# ETH_PART.net
KiCad netlist of a schematic drawn in Altium Designer
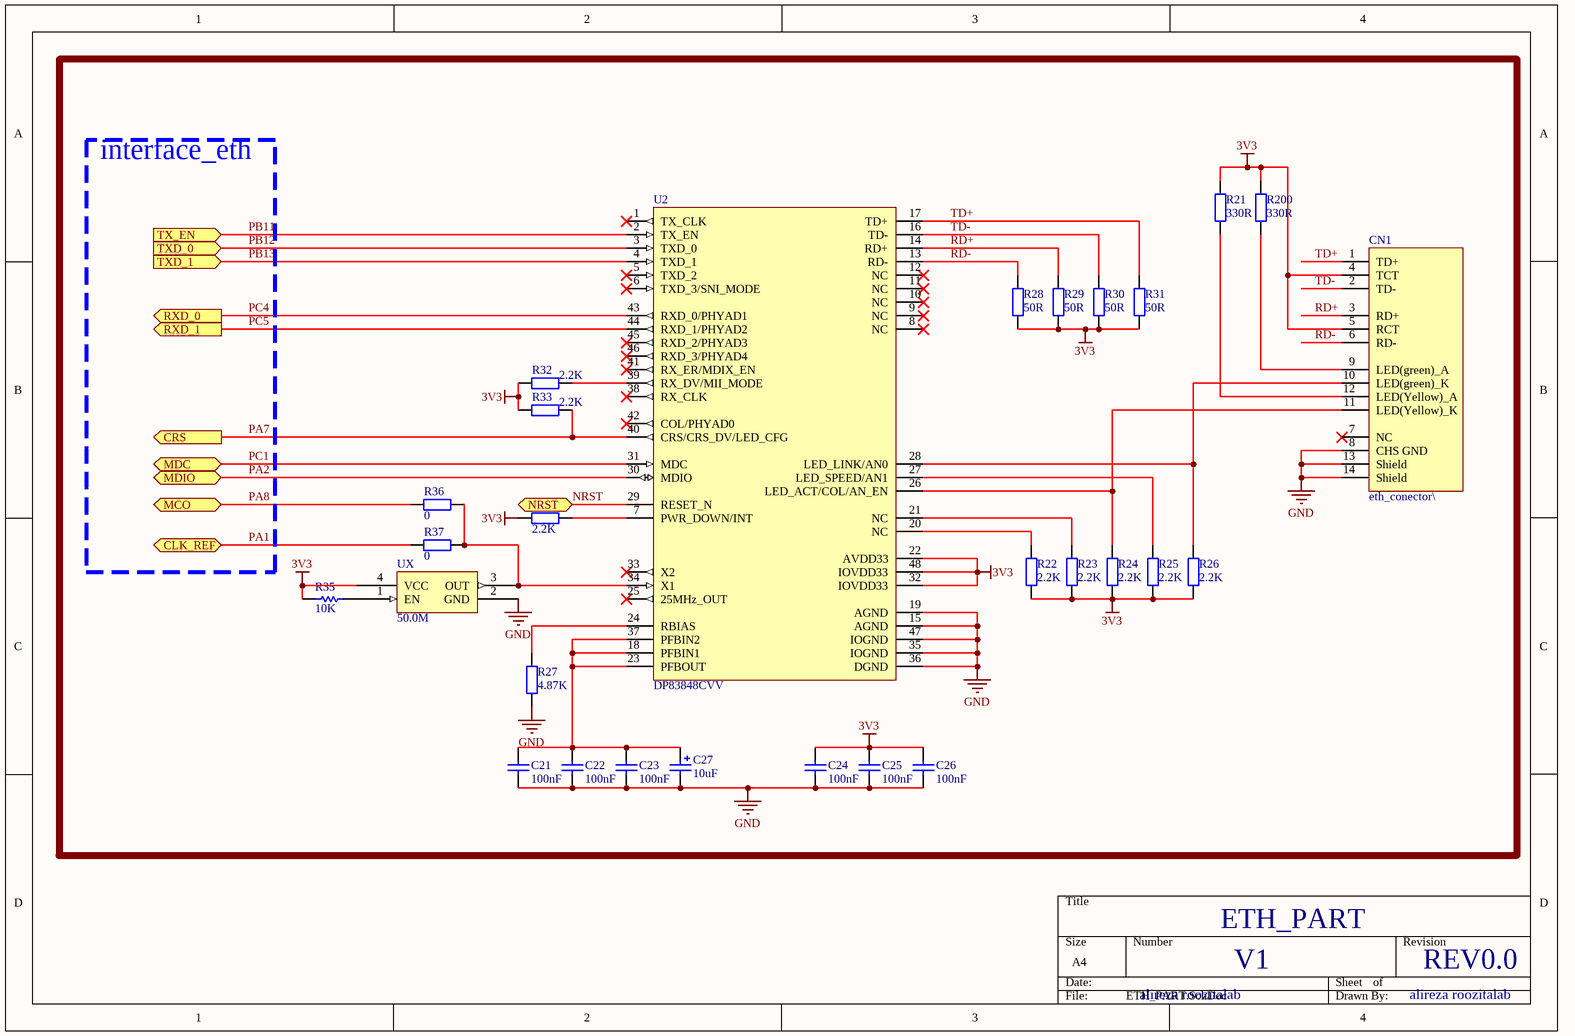
[diagram p0: ETH_PART.SchDoc]

(export (version "E")
  (design (tool "Eeschema 10.0.6"))
  (components
    (comp (ref "C21")
      (value "100nF")
      (footprint "0805.")
      (description "Capacitor")
      (fields (field (name "PUBLISHER") "Altium Limited"))
      (libsource (lib "STM32F407_144") (part "Cap"))
    )
    (comp (ref "C22")
      (value "100nF")
      (footprint "0805.")
      (description "Capacitor")
      (fields (field (name "PUBLISHER") "Altium Limited"))
      (libsource (lib "STM32F407_144") (part "Cap"))
    )
    (comp (ref "C23")
      (value "100nF")
      (footprint "0805.")
      (description "Capacitor")
      (fields (field (name "PUBLISHER") "Altium Limited"))
      (libsource (lib "STM32F407_144") (part "Cap"))
    )
    (comp (ref "C24")
      (value "100nF")
      (footprint "0805.")
      (description "Capacitor")
      (fields (field (name "PUBLISHER") "Altium Limited"))
      (libsource (lib "STM32F407_144") (part "Cap"))
    )
    (comp (ref "C25")
      (value "100nF")
      (footprint "0805.")
      (description "Capacitor")
      (fields (field (name "PUBLISHER") "Altium Limited"))
      (libsource (lib "STM32F407_144") (part "Cap"))
    )
    (comp (ref "C26")
      (value "100nF")
      (footprint "0805.")
      (description "Capacitor")
      (fields (field (name "PUBLISHER") "Altium Limited"))
      (libsource (lib "STM32F407_144") (part "Cap"))
    )
    (comp (ref "C27")
      (value "10uF")
      (footprint "C1206.")
      (description "Polarized Capacitor (Radial)")
      (fields (field (name "PUBLISHER") "Altium Limited"))
      (libsource (lib "STM32F407_144") (part "Cap Pol1"))
    )
    (comp (ref "CN1")
      (value "eth_conecto~{r}")
      (footprint "eth_conector")
      (libsource (lib "my dxp lib") (part "eth_conector{backslash}"))
    )
    (comp (ref "R21")
      (value "330R")
      (footprint "0805.")
      (description "Resistor")
      (fields (field (name "Comment") "Res2") (field (name "PUBLISHER") "Altium Limited"))
      (libsource (lib "STM32F407_144") (part "Res2"))
    )
    (comp (ref "R22")
      (value "2.2K")
      (footprint "0805.")
      (description "Resistor")
      (fields (field (name "Comment") "Res2") (field (name "PUBLISHER") "Altium Limited"))
      (libsource (lib "STM32F407_144") (part "Res2"))
    )
    (comp (ref "R23")
      (value "2.2K")
      (footprint "0805.")
      (description "Resistor")
      (fields (field (name "Comment") "Res2") (field (name "PUBLISHER") "Altium Limited"))
      (libsource (lib "STM32F407_144") (part "Res2"))
    )
    (comp (ref "R24")
      (value "2.2K")
      (footprint "0805.")
      (description "Resistor")
      (fields (field (name "Comment") "Res2") (field (name "PUBLISHER") "Altium Limited"))
      (libsource (lib "STM32F407_144") (part "Res2"))
    )
    (comp (ref "R25")
      (value "2.2K")
      (footprint "0805.")
      (description "Resistor")
      (fields (field (name "Comment") "Res2") (field (name "PUBLISHER") "Altium Limited"))
      (libsource (lib "STM32F407_144") (part "Res2"))
    )
    (comp (ref "R26")
      (value "2.2K")
      (footprint "0805.")
      (description "Resistor")
      (fields (field (name "Comment") "Res2") (field (name "PUBLISHER") "Altium Limited"))
      (libsource (lib "STM32F407_144") (part "Res2"))
    )
    (comp (ref "R27")
      (value "4.87K")
      (footprint "0805.")
      (description "Resistor")
      (fields (field (name "Comment") "Res2") (field (name "PUBLISHER") "Altium Limited"))
      (libsource (lib "STM32F407_144") (part "Res2"))
    )
    (comp (ref "R28")
      (value "50R")
      (footprint "0805.")
      (description "Resistor")
      (fields (field (name "Comment") "Res2") (field (name "PUBLISHER") "Altium Limited"))
      (libsource (lib "STM32F407_144") (part "Res2"))
    )
    (comp (ref "R29")
      (value "50R")
      (footprint "0805.")
      (description "Resistor")
      (fields (field (name "Comment") "Res2") (field (name "PUBLISHER") "Altium Limited"))
      (libsource (lib "STM32F407_144") (part "Res2"))
    )
    (comp (ref "R30")
      (value "50R")
      (footprint "0805.")
      (description "Resistor")
      (fields (field (name "Comment") "Res2") (field (name "PUBLISHER") "Altium Limited"))
      (libsource (lib "STM32F407_144") (part "Res2"))
    )
    (comp (ref "R31")
      (value "50R")
      (footprint "0805.")
      (description "Resistor")
      (fields (field (name "Comment") "Res2") (field (name "PUBLISHER") "Altium Limited"))
      (libsource (lib "STM32F407_144") (part "Res2"))
    )
    (comp (ref "R32")
      (value "2.2K")
      (footprint "0805.")
      (description "Resistor")
      (fields (field (name "Comment") "Res2") (field (name "PUBLISHER") "Altium Limited"))
      (libsource (lib "") (part "Res2_1"))
    )
    (comp (ref "R33")
      (value "2.2K")
      (footprint "0805.")
      (description "Resistor")
      (fields (field (name "Comment") "Res2") (field (name "PUBLISHER") "Altium Limited"))
      (libsource (lib "") (part "Res2_1"))
    )
    (comp (ref "R34")
      (value "2.2K")
      (footprint "0805.")
      (description "Resistor")
      (fields (field (name "Comment") "Res2") (field (name "PUBLISHER") "Altium Limited"))
      (libsource (lib "") (part "Res2_1"))
    )
    (comp (ref "R35")
      (value "10K")
      (footprint "0805.")
      (description "Resistor")
      (fields (field (name "PUBLISHER") "Altium Limited"))
      (libsource (lib "STM32F407_144") (part "Res1"))
    )
    (comp (ref "R36")
      (value "0")
      (footprint "0805.")
      (description "Resistor")
      (fields (field (name "Comment") "Res2") (field (name "PUBLISHER") "Altium Limited"))
      (libsource (lib "") (part "Res2_1"))
    )
    (comp (ref "R37")
      (value "0")
      (footprint "0805.")
      (description "Resistor")
      (fields (field (name "Comment") "Res2") (field (name "PUBLISHER") "Altium Limited"))
      (libsource (lib "") (part "Res2_1"))
    )
    (comp (ref "R200")
      (value "330R")
      (footprint "0805.")
      (description "Resistor")
      (fields (field (name "Comment") "Res2") (field (name "PUBLISHER") "Altium Limited"))
      (libsource (lib "STM32F407_144") (part "Res2"))
    )
    (comp (ref "U2")
      (value "DP83848CVV")
      (footprint "LQFP48")
      (libsource (lib "STM32F407_144") (part "DP83848CVV"))
    )
    (comp (ref "UX")
      (value "50.0M")
      (footprint "oscillator_50MHZ")
      (libsource (lib "STM32F407_144") (part "SM7745HEV-50.0M"))
    )
  )
  (nets
    (net (code "1") (name "/NRST") (class "Default")
      (node (ref "U2") (pin "29") (pinfunction "RESET_N_29") (pintype "passive"))
    )
    (net (code "2") (name "/PA1") (class "Default")
      (node (ref "R37") (pin "1") (pinfunction "1_1") (pintype "passive"))
    )
    (net (code "3") (name "/PA2") (class "Default")
      (node (ref "U2") (pin "30") (pinfunction "MDIO_30") (pintype "bidirectional"))
    )
    (net (code "4") (name "/PA7") (class "Default")
      (node (ref "R33") (pin "2") (pinfunction "2_2") (pintype "passive"))
      (node (ref "U2") (pin "40") (pinfunction "CRS/CRS_DV/LED_CFG_40") (pintype "output"))
    )
    (net (code "5") (name "/PA8") (class "Default")
      (node (ref "R36") (pin "1") (pinfunction "1_1") (pintype "passive"))
    )
    (net (code "6") (name "/PB11") (class "Default")
      (node (ref "U2") (pin "2") (pinfunction "TX_EN_2") (pintype "input"))
    )
    (net (code "7") (name "/PB12") (class "Default")
      (node (ref "U2") (pin "3") (pinfunction "TXD_0_3") (pintype "input"))
    )
    (net (code "8") (name "/PB13") (class "Default")
      (node (ref "U2") (pin "4") (pinfunction "TXD_1_4") (pintype "input"))
    )
    (net (code "9") (name "/PC1") (class "Default")
      (node (ref "U2") (pin "31") (pinfunction "MDC_31") (pintype "input"))
    )
    (net (code "10") (name "/PC4") (class "Default")
      (node (ref "U2") (pin "43") (pinfunction "RXD_0/PHYAD1_43") (pintype "output"))
    )
    (net (code "11") (name "/PC5") (class "Default")
      (node (ref "U2") (pin "44") (pinfunction "RXD_1/PHYAD2_44") (pintype "output"))
    )
    (net (code "12") (name "/RD+") (class "Default")
      (node (ref "CN1") (pin "3") (pinfunction "RD+_3") (pintype "passive"))
      (node (ref "R29") (pin "2") (pinfunction "2_2") (pintype "passive"))
      (node (ref "U2") (pin "14") (pinfunction "RD+_14") (pintype "passive"))
    )
    (net (code "13") (name "/RD-") (class "Default")
      (node (ref "CN1") (pin "6") (pinfunction "RD-_6") (pintype "passive"))
      (node (ref "R28") (pin "2") (pinfunction "2_2") (pintype "passive"))
      (node (ref "U2") (pin "13") (pinfunction "RD-_13") (pintype "passive"))
    )
    (net (code "14") (name "/TD+") (class "Default")
      (node (ref "CN1") (pin "1") (pinfunction "TD+_1") (pintype "passive"))
      (node (ref "R31") (pin "2") (pinfunction "2_2") (pintype "passive"))
      (node (ref "U2") (pin "17") (pinfunction "TD+_17") (pintype "passive"))
    )
    (net (code "15") (name "/TD-") (class "Default")
      (node (ref "CN1") (pin "2") (pinfunction "TD-_2") (pintype "passive"))
      (node (ref "R30") (pin "2") (pinfunction "2_2") (pintype "passive"))
      (node (ref "U2") (pin "16") (pinfunction "TD-_16") (pintype "passive"))
    )
    (net (code "16") (name "3V3") (class "Default")
      (node (ref "C24") (pin "1") (pinfunction "1_1") (pintype "passive"))
      (node (ref "C25") (pin "1") (pinfunction "1_1") (pintype "passive"))
      (node (ref "C26") (pin "1") (pinfunction "1_1") (pintype "passive"))
      (node (ref "CN1") (pin "4") (pinfunction "TCT_4") (pintype "passive"))
      (node (ref "CN1") (pin "5") (pinfunction "RCT_5") (pintype "passive"))
      (node (ref "R200") (pin "2") (pinfunction "2_2") (pintype "passive"))
      (node (ref "R21") (pin "2") (pinfunction "2_2") (pintype "passive"))
      (node (ref "R22") (pin "1") (pinfunction "1_1") (pintype "passive"))
      (node (ref "R23") (pin "1") (pinfunction "1_1") (pintype "passive"))
      (node (ref "R24") (pin "1") (pinfunction "1_1") (pintype "passive"))
      (node (ref "R25") (pin "1") (pinfunction "1_1") (pintype "passive"))
      (node (ref "R26") (pin "1") (pinfunction "1_1") (pintype "passive"))
      (node (ref "R28") (pin "1") (pinfunction "1_1") (pintype "passive"))
      (node (ref "R29") (pin "1") (pinfunction "1_1") (pintype "passive"))
      (node (ref "R30") (pin "1") (pinfunction "1_1") (pintype "passive"))
      (node (ref "R31") (pin "1") (pinfunction "1_1") (pintype "passive"))
      (node (ref "R32") (pin "1") (pinfunction "1_1") (pintype "passive"))
      (node (ref "R33") (pin "1") (pinfunction "1_1") (pintype "passive"))
      (node (ref "R34") (pin "1") (pinfunction "1_1") (pintype "passive"))
      (node (ref "R35") (pin "1") (pinfunction "1_1") (pintype "passive"))
      (node (ref "U2") (pin "22") (pinfunction "AVDD33_22") (pintype "passive"))
      (node (ref "U2") (pin "32") (pinfunction "IOVDD33_32") (pintype "passive"))
      (node (ref "U2") (pin "48") (pinfunction "IOVDD33_48") (pintype "passive"))
      (node (ref "UX") (pin "4") (pinfunction "VCC_4") (pintype "passive"))
    )
    (net (code "17") (name "GND") (class "Default")
      (node (ref "C21") (pin "2") (pinfunction "2_2") (pintype "passive"))
      (node (ref "C22") (pin "2") (pinfunction "2_2") (pintype "passive"))
      (node (ref "C23") (pin "2") (pinfunction "2_2") (pintype "passive"))
      (node (ref "C24") (pin "2") (pinfunction "2_2") (pintype "passive"))
      (node (ref "C25") (pin "2") (pinfunction "2_2") (pintype "passive"))
      (node (ref "C26") (pin "2") (pinfunction "2_2") (pintype "passive"))
      (node (ref "C27") (pin "2") (pinfunction "2_2") (pintype "passive"))
      (node (ref "CN1") (pin "13") (pinfunction "Shield_13") (pintype "passive"))
      (node (ref "CN1") (pin "14") (pinfunction "Shield_14") (pintype "passive"))
      (node (ref "CN1") (pin "8") (pinfunction "CHS_GND_8") (pintype "passive"))
      (node (ref "R27") (pin "1") (pinfunction "1_1") (pintype "passive"))
      (node (ref "U2") (pin "15") (pinfunction "AGND_15") (pintype "passive"))
      (node (ref "U2") (pin "19") (pinfunction "AGND_19") (pintype "passive"))
      (node (ref "U2") (pin "35") (pinfunction "IOGND_35") (pintype "passive"))
      (node (ref "U2") (pin "36") (pinfunction "DGND_36") (pintype "passive"))
      (node (ref "U2") (pin "47") (pinfunction "IOGND_47") (pintype "passive"))
      (node (ref "UX") (pin "2") (pinfunction "GND_2") (pintype "passive"))
    )
    (net (code "18") (name "Net-(CN1-LED(Yellow)_A)") (class "Default")
      (node (ref "CN1") (pin "12") (pinfunction "LED(Yellow)_A_12") (pintype "passive"))
      (node (ref "R21") (pin "1") (pinfunction "1_1") (pintype "passive"))
    )
    (net (code "19") (name "Net-(CN1-LED(Yellow)_K)") (class "Default")
      (node (ref "CN1") (pin "11") (pinfunction "LED(Yellow)_K_11") (pintype "passive"))
      (node (ref "R24") (pin "2") (pinfunction "2_2") (pintype "passive"))
      (node (ref "U2") (pin "26") (pinfunction "LED_ACT/COL/AN_EN_26") (pintype "passive"))
    )
    (net (code "20") (name "Net-(CN1-LED(green)_A)") (class "Default")
      (node (ref "CN1") (pin "9") (pinfunction "LED(green)_A_9") (pintype "passive"))
      (node (ref "R200") (pin "1") (pinfunction "1_1") (pintype "passive"))
    )
    (net (code "21") (name "Net-(CN1-LED(green)_K)") (class "Default")
      (node (ref "CN1") (pin "10") (pinfunction "LED(green)_K_10") (pintype "passive"))
      (node (ref "R26") (pin "2") (pinfunction "2_2") (pintype "passive"))
      (node (ref "U2") (pin "28") (pinfunction "LED_LINK/AN0_28") (pintype "passive"))
    )
    (net (code "22") (name "Net-(R22-Pad2)") (class "Default")
      (node (ref "R22") (pin "2") (pinfunction "2_2") (pintype "passive"))
      (node (ref "U2") (pin "20") (pinfunction "NC_20") (pintype "passive"))
    )
    (net (code "23") (name "Net-(R23-Pad2)") (class "Default")
      (node (ref "R23") (pin "2") (pinfunction "2_2") (pintype "passive"))
      (node (ref "U2") (pin "21") (pinfunction "NC_21") (pintype "passive"))
    )
    (net (code "24") (name "Net-(U2-LED_SPEED{slash}AN1)") (class "Default")
      (node (ref "R25") (pin "2") (pinfunction "2_2") (pintype "passive"))
      (node (ref "U2") (pin "27") (pinfunction "LED_SPEED/AN1_27") (pintype "passive"))
    )
    (net (code "25") (name "Net-(U2-PFBIN1)") (class "Default")
      (node (ref "C21") (pin "1") (pinfunction "1_1") (pintype "passive"))
      (node (ref "C22") (pin "1") (pinfunction "1_1") (pintype "passive"))
      (node (ref "C23") (pin "1") (pinfunction "1_1") (pintype "passive"))
      (node (ref "C27") (pin "1") (pinfunction "1_1") (pintype "passive"))
      (node (ref "U2") (pin "18") (pinfunction "PFBIN1_18") (pintype "passive"))
      (node (ref "U2") (pin "23") (pinfunction "PFBOUT_23") (pintype "passive"))
      (node (ref "U2") (pin "37") (pinfunction "PFBIN2_37") (pintype "passive"))
    )
    (net (code "26") (name "Net-(U2-PWR_DOWN{slash}INT)") (class "Default")
      (node (ref "R34") (pin "2") (pinfunction "2_2") (pintype "passive"))
      (node (ref "U2") (pin "7") (pinfunction "PWR_DOWN/INT_7") (pintype "passive"))
    )
    (net (code "27") (name "Net-(U2-RBIAS)") (class "Default")
      (node (ref "R27") (pin "2") (pinfunction "2_2") (pintype "passive"))
      (node (ref "U2") (pin "24") (pinfunction "RBIAS_24") (pintype "passive"))
    )
    (net (code "28") (name "Net-(U2-RX_DV{slash}MII_MODE)") (class "Default")
      (node (ref "R32") (pin "2") (pinfunction "2_2") (pintype "passive"))
      (node (ref "U2") (pin "39") (pinfunction "RX_DV/MII_MODE_39") (pintype "output"))
    )
    (net (code "29") (name "Net-(U2-X1)") (class "Default")
      (node (ref "R36") (pin "2") (pinfunction "2_2") (pintype "passive"))
      (node (ref "R37") (pin "2") (pinfunction "2_2") (pintype "passive"))
      (node (ref "U2") (pin "34") (pinfunction "X1_34") (pintype "input"))
      (node (ref "UX") (pin "3") (pinfunction "OUT_3") (pintype "output"))
    )
    (net (code "30") (name "Net-(UX-EN)") (class "Default")
      (node (ref "R35") (pin "2") (pinfunction "2_2") (pintype "passive"))
      (node (ref "UX") (pin "1") (pinfunction "EN_1") (pintype "input"))
    )
    (net (code "31") (name "unconnected-(CN1-NC-Pad7)") (class "Default")
      (node (ref "CN1") (pin "7") (pinfunction "NC_7") (pintype "passive+no_connect"))
    )
    (net (code "32") (name "unconnected-(U2-25MHz_OUT-Pad25)") (class "Default")
      (node (ref "U2") (pin "25") (pinfunction "25MHz_OUT_25") (pintype "output+no_connect"))
    )
    (net (code "33") (name "unconnected-(U2-COL{slash}PHYAD0-Pad42)") (class "Default")
      (node (ref "U2") (pin "42") (pinfunction "COL/PHYAD0_42") (pintype "output+no_connect"))
    )
    (net (code "34") (name "unconnected-(U2-NC-Pad8)") (class "Default")
      (node (ref "U2") (pin "8") (pinfunction "NC_8") (pintype "passive+no_connect"))
    )
    (net (code "35") (name "unconnected-(U2-NC-Pad9)") (class "Default")
      (node (ref "U2") (pin "9") (pinfunction "NC_9") (pintype "passive+no_connect"))
    )
    (net (code "36") (name "unconnected-(U2-NC-Pad10)") (class "Default")
      (node (ref "U2") (pin "10") (pinfunction "NC_10") (pintype "passive+no_connect"))
    )
    (net (code "37") (name "unconnected-(U2-NC-Pad11)") (class "Default")
      (node (ref "U2") (pin "11") (pinfunction "NC_11") (pintype "passive+no_connect"))
    )
    (net (code "38") (name "unconnected-(U2-NC-Pad12)") (class "Default")
      (node (ref "U2") (pin "12") (pinfunction "NC_12") (pintype "passive+no_connect"))
    )
    (net (code "39") (name "unconnected-(U2-RXD_2{slash}PHYAD3-Pad45)") (class "Default")
      (node (ref "U2") (pin "45") (pinfunction "RXD_2/PHYAD3_45") (pintype "output+no_connect"))
    )
    (net (code "40") (name "unconnected-(U2-RXD_3{slash}PHYAD4-Pad46)") (class "Default")
      (node (ref "U2") (pin "46") (pinfunction "RXD_3/PHYAD4_46") (pintype "output+no_connect"))
    )
    (net (code "41") (name "unconnected-(U2-RX_CLK-Pad38)") (class "Default")
      (node (ref "U2") (pin "38") (pinfunction "RX_CLK_38") (pintype "output+no_connect"))
    )
    (net (code "42") (name "unconnected-(U2-RX_ER{slash}MDIX_EN-Pad41)") (class "Default")
      (node (ref "U2") (pin "41") (pinfunction "RX_ER/MDIX_EN_41") (pintype "output+no_connect"))
    )
    (net (code "43") (name "unconnected-(U2-TXD_2-Pad5)") (class "Default")
      (node (ref "U2") (pin "5") (pinfunction "TXD_2_5") (pintype "input+no_connect"))
    )
    (net (code "44") (name "unconnected-(U2-TXD_3{slash}SNI_MODE-Pad6)") (class "Default")
      (node (ref "U2") (pin "6") (pinfunction "TXD_3/SNI_MODE_6") (pintype "input+no_connect"))
    )
    (net (code "45") (name "unconnected-(U2-TX_CLK-Pad1)") (class "Default")
      (node (ref "U2") (pin "1") (pinfunction "TX_CLK_1") (pintype "output+no_connect"))
    )
    (net (code "46") (name "unconnected-(U2-X2-Pad33)") (class "Default")
      (node (ref "U2") (pin "33") (pinfunction "X2_33") (pintype "output+no_connect"))
    )
  )
)
